# LED_Breakout_Board_V6.net
KiCad netlist of a schematic drawn in EAGLE
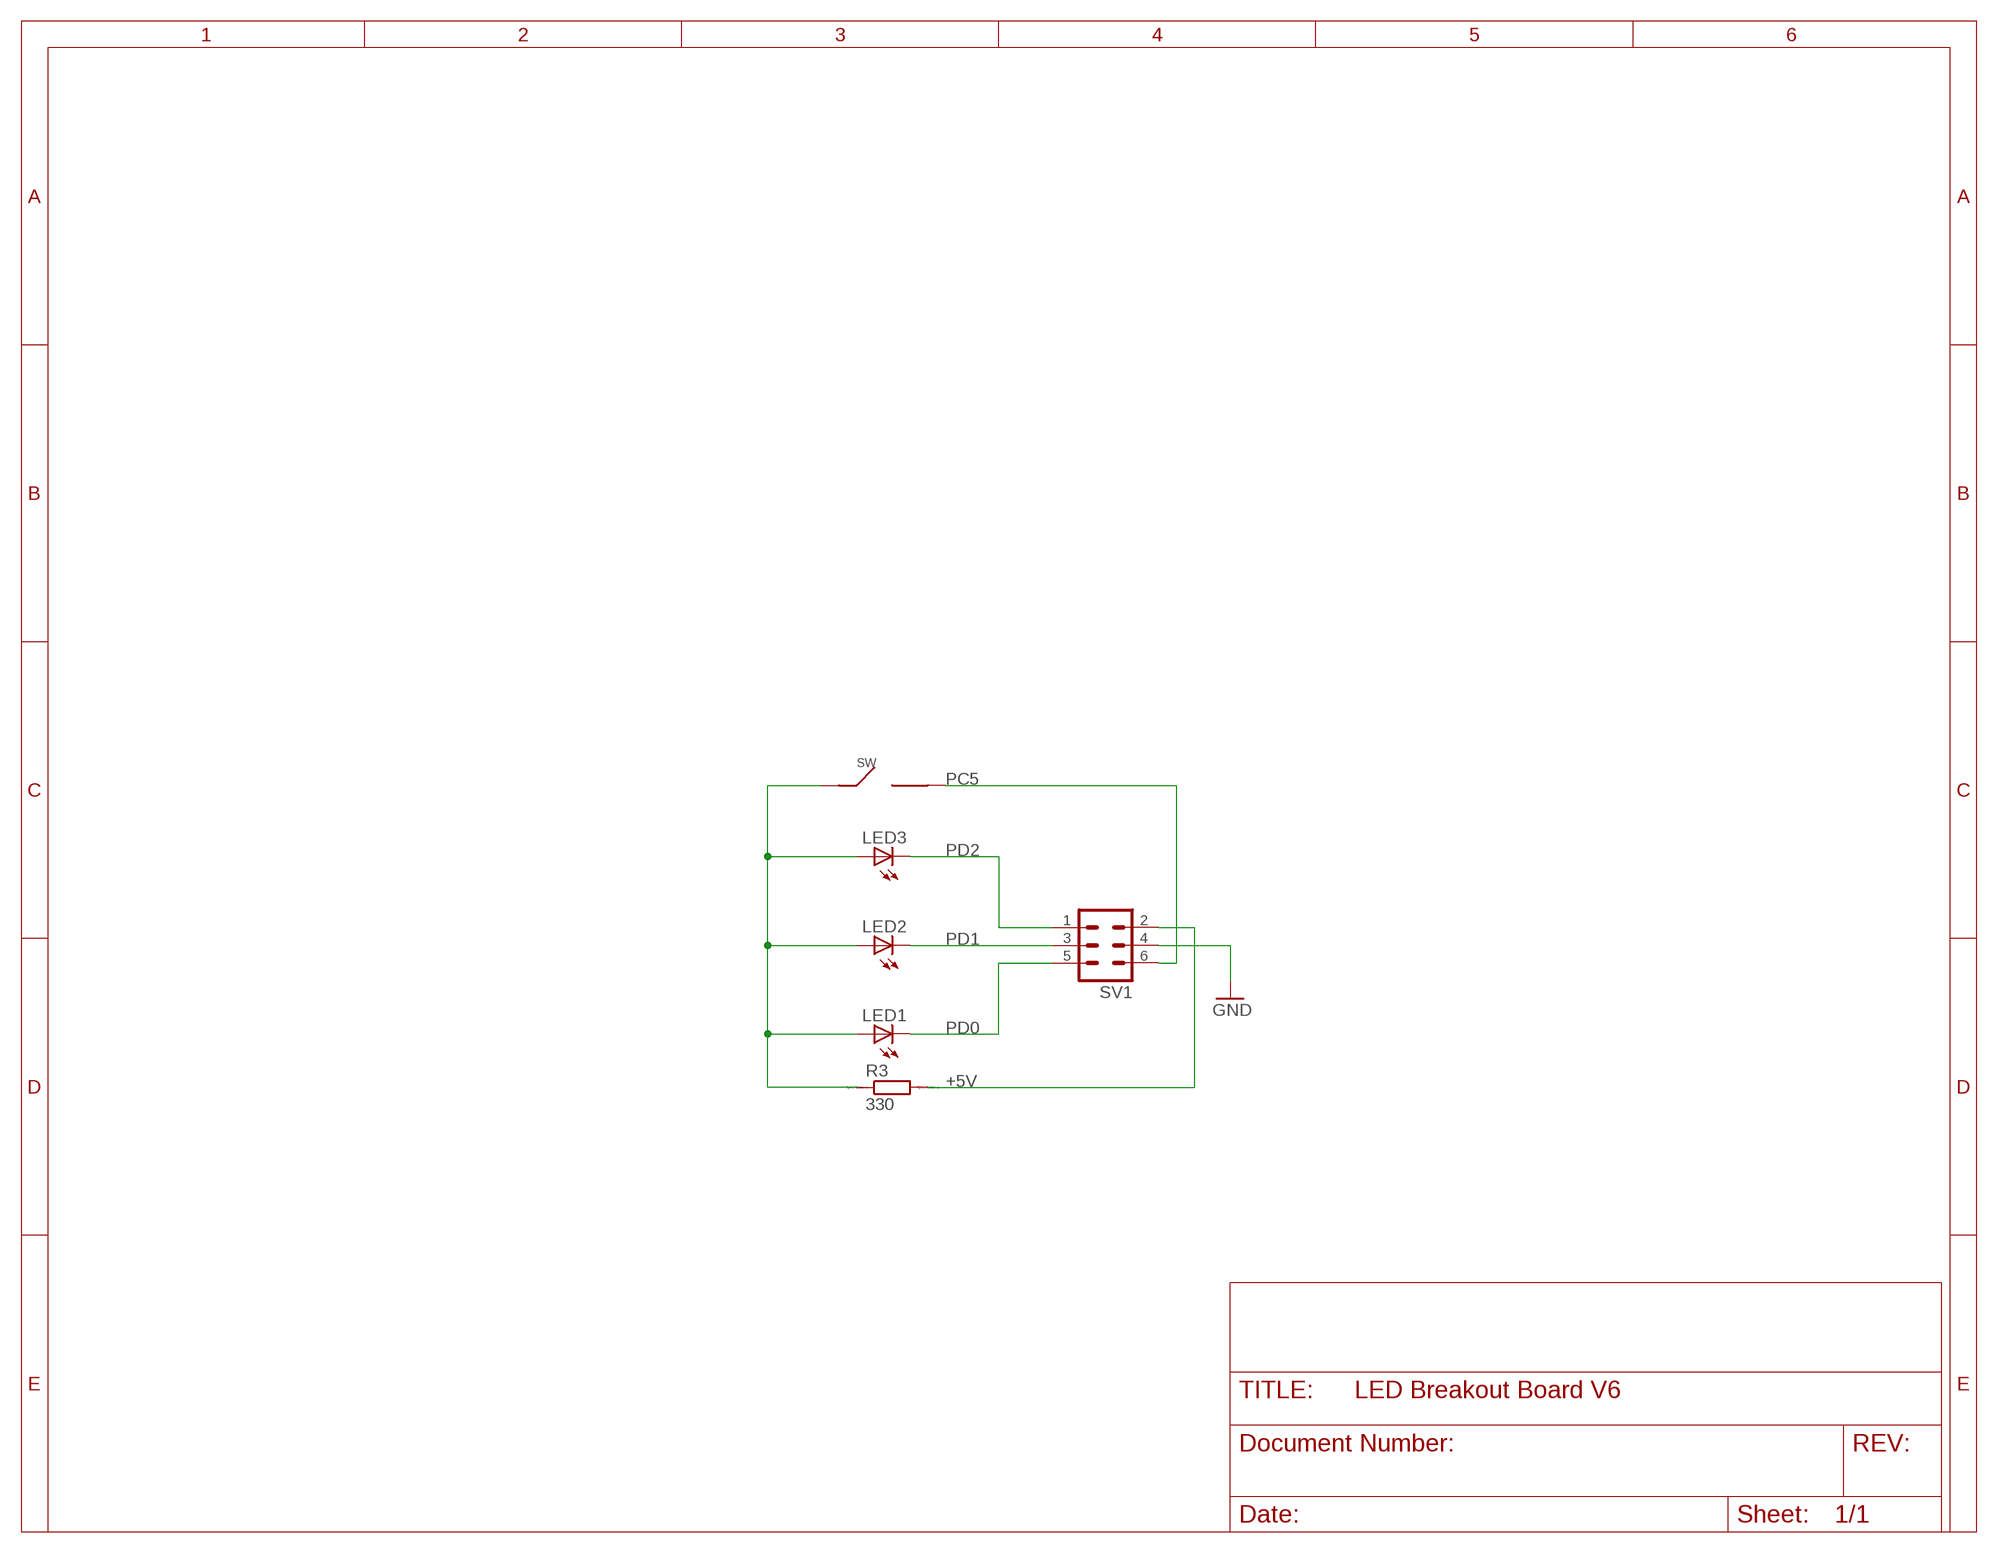
[diagram p0: schematic, sheet 1]

(export (version "E")
  (design (tool "Eeschema 10.0.6"))
  (components
    (comp (ref "LED1")
      (value "LED10MM")
      (footprint "eagle-import:LED10MM")
      (libsource (lib "eagle-import") (part "LED10MM"))
    )
    (comp (ref "LED2")
      (value "LED10MM")
      (footprint "eagle-import:LED10MM")
      (libsource (lib "eagle-import") (part "LED10MM"))
    )
    (comp (ref "LED3")
      (value "LED10MM")
      (footprint "eagle-import:LED10MM")
      (libsource (lib "eagle-import") (part "LED10MM"))
    )
    (comp (ref "R3")
      (value "330")
      (footprint "eagle-import:R0805")
      (libsource (lib "eagle-import") (part "R-EU_R0805"))
    )
    (comp (ref "SV1")
      (value "MA03-2")
      (footprint "eagle-import:MA03-2")
      (libsource (lib "eagle-import") (part "MA03-2"))
    )
    (comp (ref "SW")
      (value "PUSHBUTTON")
      (footprint "eagle-import:PUSHBUTTON")
      (libsource (lib "eagle-import") (part "PUSHBUTTON"))
    )
  )
  (nets
    (net (code "1") (name "/+5V") (class "Default")
      (node (ref "R3") (pin "2") (pinfunction "2_2") (pintype "passive"))
      (node (ref "SV1") (pin "2") (pinfunction "2_2") (pintype "passive"))
    )
    (net (code "2") (name "/PC5") (class "Default")
      (node (ref "SV1") (pin "6") (pinfunction "6_6") (pintype "passive"))
      (node (ref "SW") (pin "OUT") (pinfunction "OUT_OUT") (pintype "bidirectional"))
    )
    (net (code "3") (name "/PD0") (class "Default")
      (node (ref "LED1") (pin "K") (pinfunction "C_K") (pintype "passive"))
      (node (ref "SV1") (pin "5") (pinfunction "5_5") (pintype "passive"))
    )
    (net (code "4") (name "/PD1") (class "Default")
      (node (ref "LED2") (pin "K") (pinfunction "C_K") (pintype "passive"))
      (node (ref "SV1") (pin "3") (pinfunction "3_3") (pintype "passive"))
    )
    (net (code "5") (name "/PD2") (class "Default")
      (node (ref "LED3") (pin "K") (pinfunction "C_K") (pintype "passive"))
      (node (ref "SV1") (pin "1") (pinfunction "1_1") (pintype "passive"))
    )
    (net (code "6") (name "GND") (class "Default")
      (node (ref "SV1") (pin "4") (pinfunction "4_4") (pintype "passive"))
    )
    (net (code "7") (name "Net-(LED1-PadA)") (class "Default")
      (node (ref "LED1") (pin "A") (pinfunction "A_A") (pintype "passive"))
      (node (ref "LED2") (pin "A") (pinfunction "A_A") (pintype "passive"))
      (node (ref "LED3") (pin "A") (pinfunction "A_A") (pintype "passive"))
      (node (ref "R3") (pin "1") (pinfunction "1_1") (pintype "passive"))
      (node (ref "SW") (pin "IN") (pinfunction "IN_IN") (pintype "bidirectional"))
    )
  )
)
